# Sheet3.net
KiCad netlist of a schematic drawn in Altium Designer
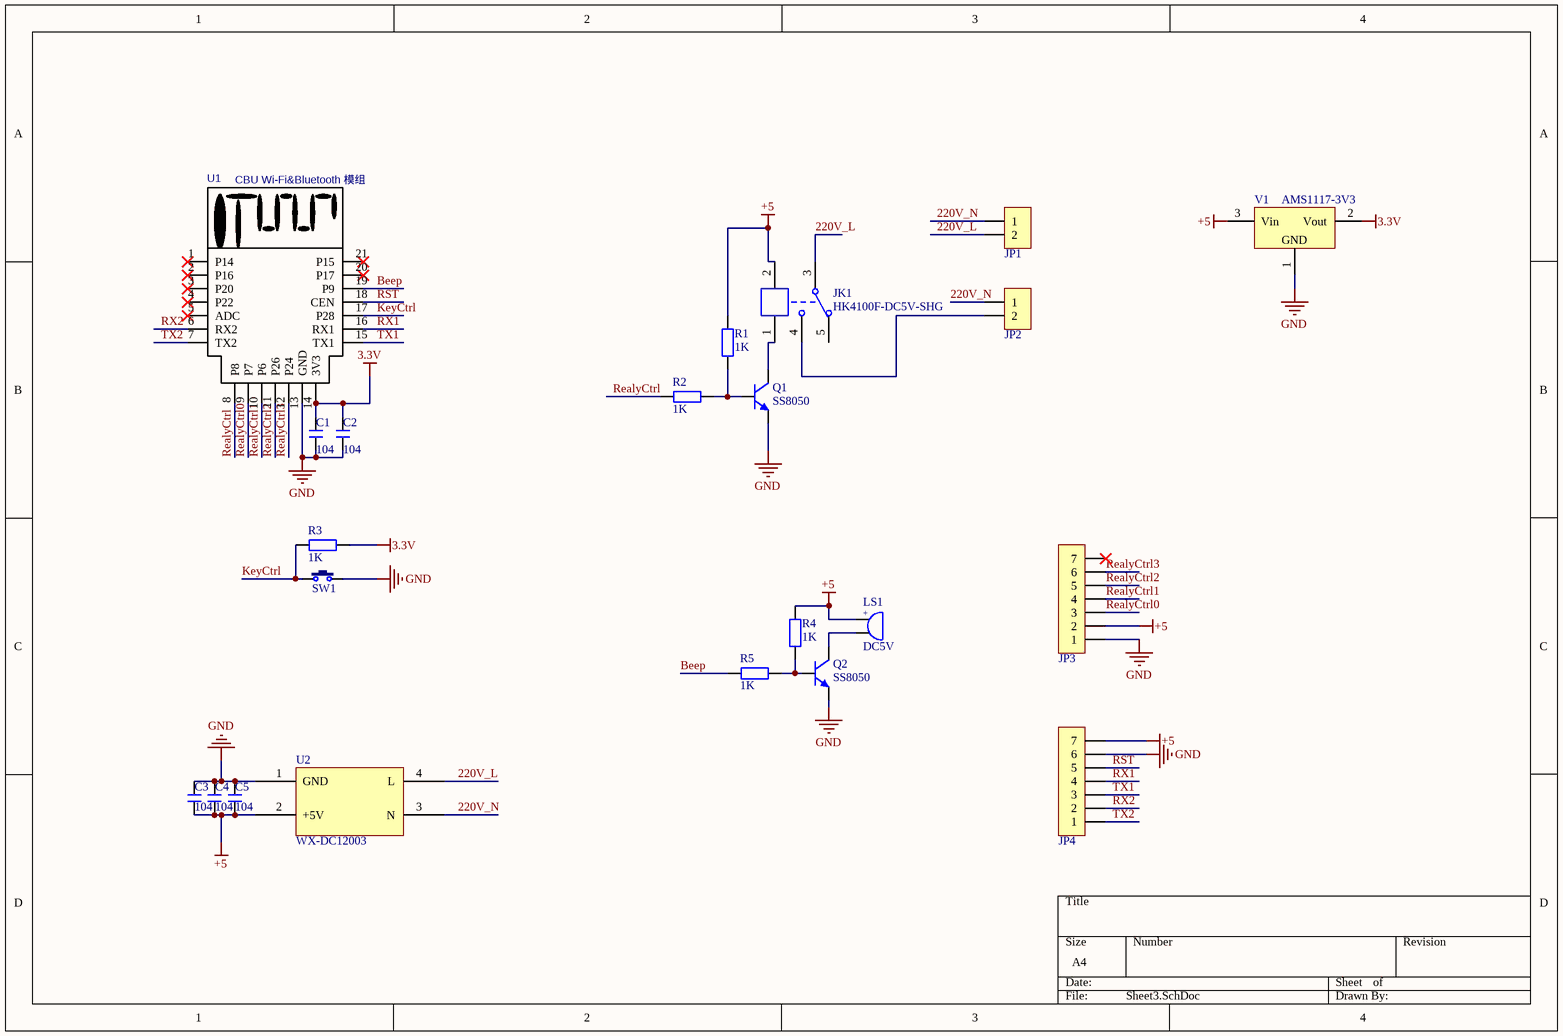
[diagram p0: Sheet3.SchDoc]

(export (version "E")
  (design (tool "Eeschema 10.0.6"))
  (components
    (comp (ref "C1")
      (value "104")
      (footprint "C 0805_M")
      (description "无极性贴片电容")
      (fields (field (name "版权归属") "源创客"))
      (libsource (lib "3.1   - 电阻-电容-电感") (part "C"))
    )
    (comp (ref "C2")
      (value "104")
      (footprint "C 0805_M")
      (description "无极性贴片电容")
      (fields (field (name "版权归属") "源创客"))
      (libsource (lib "3.1   - 电阻-电容-电感") (part "C"))
    )
    (comp (ref "C3")
      (value "104")
      (footprint "C 0805_M")
      (description "无极性贴片电容")
      (fields (field (name "版权归属") "源创客"))
      (libsource (lib "3.1   - 电阻-电容-电感") (part "C"))
    )
    (comp (ref "C4")
      (value "104")
      (footprint "C 0805_M")
      (description "无极性贴片电容")
      (fields (field (name "版权归属") "源创客"))
      (libsource (lib "3.1   - 电阻-电容-电感") (part "C"))
    )
    (comp (ref "C5")
      (value "104")
      (footprint "C 0805_M")
      (description "无极性贴片电容")
      (fields (field (name "版权归属") "源创客"))
      (libsource (lib "3.1   - 电阻-电容-电感") (part "C"))
    )
    (comp (ref "JK1")
      (value "HK4100F-DC5V-SHG")
      (footprint "HK4100F")
      (description "一组转换")
      (fields (field (name "版权归属") "源创客"))
      (libsource (lib "7.1   - 继电器") (part "HK4100F"))
    )
    (comp (ref "JP1")
      (value "HDR-1X2")
      (footprint "KF128-3.81-2P")
      (description "2P接插件")
      (fields (field (name "版权归属") "源创客"))
      (libsource (lib "4.7   - 接插件-脚距3.81") (part "Header 2"))
    )
    (comp (ref "JP2")
      (value "HDR-1X2")
      (footprint "KF128-3.81-2P")
      (description "2P接插件")
      (fields (field (name "版权归属") "源创客"))
      (libsource (lib "4.7   - 接插件-脚距3.81") (part "Header 2"))
    )
    (comp (ref "JP3")
      (value "HDR-1X7")
      (footprint "HDR2.54-M-LI-7P")
      (description "7P接插件")
      (fields (field (name "版权归属") "源创客"))
      (libsource (lib "4.5   - 接插件-脚距2.54") (part "Header 7"))
    )
    (comp (ref "JP4")
      (value "HDR-1X7")
      (footprint "HDR2.54-M-LI-7P")
      (description "7P接插件")
      (fields (field (name "版权归属") "源创客"))
      (libsource (lib "4.5   - 接插件-脚距2.54") (part "Header 7"))
    )
    (comp (ref "LS1")
      (value "DC5V")
      (footprint "BEEP 7.6X12X7.5")
      (description "蜂鸣器")
      (fields (field (name "版权归属") "源创客"))
      (libsource (lib "15.1 - 未分类器件") (part "BEEP"))
    )
    (comp (ref "Q1")
      (value "SS8050")
      (footprint "SOT23-3M")
      (description "高频放大-NPN型")
      (fields (field (name "版权归属") "源创客"))
      (libsource (lib "6.2   - 三极管") (part "8050-SMD"))
    )
    (comp (ref "Q2")
      (value "SS8050")
      (footprint "SOT23-3M")
      (description "高频放大-NPN型")
      (fields (field (name "版权归属") "源创客"))
      (libsource (lib "6.2   - 三极管") (part "8050-SMD"))
    )
    (comp (ref "R1")
      (value "1K")
      (footprint "R 0805_M")
      (description "贴片电阻")
      (fields (field (name "版权归属") "源创客"))
      (libsource (lib "3.1   - 电阻-电容-电感") (part "R"))
    )
    (comp (ref "R2")
      (value "1K")
      (footprint "R 0805_M")
      (description "贴片电阻")
      (fields (field (name "版权归属") "源创客"))
      (libsource (lib "3.1   - 电阻-电容-电感") (part "R"))
    )
    (comp (ref "R3")
      (value "1K")
      (footprint "R 0805_M")
      (description "贴片电阻")
      (fields (field (name "版权归属") "源创客"))
      (libsource (lib "3.1   - 电阻-电容-电感") (part "R"))
    )
    (comp (ref "R4")
      (value "1K")
      (footprint "R 0805_M")
      (description "贴片电阻")
      (fields (field (name "版权归属") "源创客"))
      (libsource (lib "3.1   - 电阻-电容-电感") (part "R"))
    )
    (comp (ref "R5")
      (value "1K")
      (footprint "R 0805_M")
      (description "贴片电阻")
      (fields (field (name "版权归属") "源创客"))
      (libsource (lib "3.1   - 电阻-电容-电感") (part "R"))
    )
    (comp (ref "SW1")
      (value "3x6x5")
      (footprint "TSW SMD-3*6*2.5")
      (description "3x6轻触开关")
      (fields (field (name "版权归属") "源创客"))
      (libsource (lib "5.1   - 按键-开关") (part "TSW 3x6"))
    )
    (comp (ref "U1")
      (value "CBU Wi-Fi&Bluetooth 模组")
      (footprint "CBU WIFI&BLUETOOTH")
      (fields (field (name "CONTRIBUTOR") "chenlf"))
      (libsource (lib "13.1 - 模块") (part "CBU"))
    )
    (comp (ref "U2")
      (value "WX-DC12003")
      (footprint "WX-DC12003")
      (description "wx-DC12003 220V转5V模块")
      (libsource (lib "封装") (part "WX-DC12003"))
    )
    (comp (ref "V1")
      (value "AMS1117-3V3")
      (footprint "SOT223_L")
      (description "三端稳压芯片")
      (fields (field (name "版权归属") "源创客"))
      (libsource (lib "1.3   - 电源类芯片") (part "AMS1117"))
    )
  )
  (nets
    (net (code "1") (name "+5") (class "Default")
      (node (ref "C3") (pin "1") (pinfunction "1_1") (pintype "passive"))
      (node (ref "C4") (pin "1") (pinfunction "1_1") (pintype "passive"))
      (node (ref "C5") (pin "1") (pinfunction "1_1") (pintype "passive"))
      (node (ref "JK1") (pin "2") (pinfunction "2_2") (pintype "passive"))
      (node (ref "JP3") (pin "2") (pinfunction "2_2") (pintype "passive"))
      (node (ref "JP4") (pin "7") (pinfunction "7_7") (pintype "passive"))
      (node (ref "LS1") (pin "1") (pinfunction "1_1") (pintype "passive"))
      (node (ref "R1") (pin "2") (pinfunction "2_2") (pintype "passive"))
      (node (ref "R4") (pin "2") (pinfunction "2_2") (pintype "passive"))
      (node (ref "U2") (pin "2") (pinfunction "+5V_2") (pintype "passive"))
      (node (ref "V1") (pin "3") (pinfunction "Vin_3") (pintype "passive"))
    )
    (net (code "2") (name "/220V_L") (class "Default")
      (node (ref "JK1") (pin "3") (pinfunction "3_3") (pintype "passive"))
      (node (ref "JP1") (pin "2") (pinfunction "2_2") (pintype "passive"))
      (node (ref "U2") (pin "4") (pinfunction "L_4") (pintype "passive"))
    )
    (net (code "3") (name "/220V_N") (class "Default")
      (node (ref "JP1") (pin "1") (pinfunction "1_1") (pintype "passive"))
      (node (ref "JP2") (pin "1") (pinfunction "1_1") (pintype "passive"))
      (node (ref "U2") (pin "3") (pinfunction "N_3") (pintype "passive"))
    )
    (net (code "4") (name "/Beep") (class "Default")
      (node (ref "R5") (pin "1") (pinfunction "1_1") (pintype "passive"))
      (node (ref "U1") (pin "19") (pinfunction "P9_19") (pintype "passive"))
    )
    (net (code "5") (name "/KeyCtrl") (class "Default")
      (node (ref "R3") (pin "2") (pinfunction "2_2") (pintype "passive"))
      (node (ref "SW1") (pin "1") (pinfunction "1_1") (pintype "passive"))
      (node (ref "U1") (pin "17") (pinfunction "P28_17") (pintype "passive"))
    )
    (net (code "6") (name "/RST") (class "Default")
      (node (ref "JP4") (pin "5") (pinfunction "5_5") (pintype "passive"))
      (node (ref "U1") (pin "18") (pinfunction "CEN_18") (pintype "passive"))
    )
    (net (code "7") (name "/RX1") (class "Default")
      (node (ref "JP4") (pin "4") (pinfunction "4_4") (pintype "passive"))
      (node (ref "U1") (pin "16") (pinfunction "RX1_16") (pintype "passive"))
    )
    (net (code "8") (name "/RX2") (class "Default")
      (node (ref "JP4") (pin "2") (pinfunction "2_2") (pintype "passive"))
      (node (ref "U1") (pin "6") (pinfunction "RX2_6") (pintype "passive"))
    )
    (net (code "9") (name "/RealyCtrl") (class "Default")
      (node (ref "R2") (pin "1") (pinfunction "1_1") (pintype "passive"))
      (node (ref "U1") (pin "8") (pinfunction "P8_8") (pintype "passive"))
    )
    (net (code "10") (name "/RealyCtrl0") (class "Default")
      (node (ref "JP3") (pin "3") (pinfunction "3_3") (pintype "passive"))
      (node (ref "U1") (pin "9") (pinfunction "P7_9") (pintype "passive"))
    )
    (net (code "11") (name "/RealyCtrl1") (class "Default")
      (node (ref "JP3") (pin "4") (pinfunction "4_4") (pintype "passive"))
      (node (ref "U1") (pin "10") (pinfunction "P6_10") (pintype "passive"))
    )
    (net (code "12") (name "/RealyCtrl2") (class "Default")
      (node (ref "JP3") (pin "5") (pinfunction "5_5") (pintype "passive"))
      (node (ref "U1") (pin "11") (pinfunction "P26_11") (pintype "passive"))
    )
    (net (code "13") (name "/RealyCtrl3") (class "Default")
      (node (ref "JP3") (pin "6") (pinfunction "6_6") (pintype "passive"))
      (node (ref "U1") (pin "12") (pinfunction "P24_12") (pintype "passive"))
    )
    (net (code "14") (name "/TX1") (class "Default")
      (node (ref "JP4") (pin "3") (pinfunction "3_3") (pintype "passive"))
      (node (ref "U1") (pin "15") (pinfunction "TX1_15") (pintype "passive"))
    )
    (net (code "15") (name "/TX2") (class "Default")
      (node (ref "JP4") (pin "1") (pinfunction "1_1") (pintype "passive"))
      (node (ref "U1") (pin "7") (pinfunction "TX2_7") (pintype "passive"))
    )
    (net (code "16") (name "3.3V") (class "Default")
      (node (ref "C1") (pin "2") (pinfunction "2_2") (pintype "passive"))
      (node (ref "C2") (pin "2") (pinfunction "2_2") (pintype "passive"))
      (node (ref "R3") (pin "1") (pinfunction "1_1") (pintype "passive"))
      (node (ref "U1") (pin "14") (pinfunction "3V3_14") (pintype "passive"))
      (node (ref "V1") (pin "2") (pinfunction "Vout_2") (pintype "passive"))
    )
    (net (code "17") (name "GND") (class "Default")
      (node (ref "C1") (pin "1") (pinfunction "1_1") (pintype "passive"))
      (node (ref "C2") (pin "1") (pinfunction "1_1") (pintype "passive"))
      (node (ref "C3") (pin "2") (pinfunction "2_2") (pintype "passive"))
      (node (ref "C4") (pin "2") (pinfunction "2_2") (pintype "passive"))
      (node (ref "C5") (pin "2") (pinfunction "2_2") (pintype "passive"))
      (node (ref "JP3") (pin "1") (pinfunction "1_1") (pintype "passive"))
      (node (ref "JP4") (pin "6") (pinfunction "6_6") (pintype "passive"))
      (node (ref "Q1") (pin "2") (pinfunction "E_2") (pintype "passive"))
      (node (ref "Q2") (pin "2") (pinfunction "E_2") (pintype "passive"))
      (node (ref "SW1") (pin "2") (pinfunction "2_2") (pintype "passive"))
      (node (ref "U1") (pin "13") (pinfunction "GND_13") (pintype "passive"))
      (node (ref "U2") (pin "1") (pinfunction "GND_1") (pintype "passive"))
      (node (ref "V1") (pin "1") (pinfunction "GND_1") (pintype "passive"))
    )
    (net (code "18") (name "Net-(JK1-Pad4)") (class "Default")
      (node (ref "JK1") (pin "4") (pinfunction "4_4") (pintype "passive"))
      (node (ref "JP2") (pin "2") (pinfunction "2_2") (pintype "passive"))
    )
    (net (code "19") (name "Net-(Q1-B)") (class "Default")
      (node (ref "Q1") (pin "1") (pinfunction "B_1") (pintype "passive"))
      (node (ref "R1") (pin "1") (pinfunction "1_1") (pintype "passive"))
      (node (ref "R2") (pin "2") (pinfunction "2_2") (pintype "passive"))
    )
    (net (code "20") (name "Net-(Q1-C)") (class "Default")
      (node (ref "JK1") (pin "1") (pinfunction "1_1") (pintype "passive"))
      (node (ref "Q1") (pin "3") (pinfunction "C_3") (pintype "passive"))
    )
    (net (code "21") (name "Net-(Q2-B)") (class "Default")
      (node (ref "Q2") (pin "1") (pinfunction "B_1") (pintype "passive"))
      (node (ref "R4") (pin "1") (pinfunction "1_1") (pintype "passive"))
      (node (ref "R5") (pin "2") (pinfunction "2_2") (pintype "passive"))
    )
    (net (code "22") (name "Net-(Q2-C)") (class "Default")
      (node (ref "LS1") (pin "2") (pinfunction "2_2") (pintype "passive"))
      (node (ref "Q2") (pin "3") (pinfunction "C_3") (pintype "passive"))
    )
    (net (code "23") (name "unconnected-(JK1-Pad5)") (class "Default")
      (node (ref "JK1") (pin "5") (pinfunction "5_5") (pintype "passive"))
    )
    (net (code "24") (name "unconnected-(JP3-Pad7)") (class "Default")
      (node (ref "JP3") (pin "7") (pinfunction "7_7") (pintype "passive+no_connect"))
    )
    (net (code "25") (name "unconnected-(U1-ADC-Pad5)") (class "Default")
      (node (ref "U1") (pin "5") (pinfunction "ADC_5") (pintype "passive+no_connect"))
    )
    (net (code "26") (name "unconnected-(U1-P14-Pad1)") (class "Default")
      (node (ref "U1") (pin "1") (pinfunction "P14_1") (pintype "passive+no_connect"))
    )
    (net (code "27") (name "unconnected-(U1-P15-Pad21)") (class "Default")
      (node (ref "U1") (pin "21") (pinfunction "P15_21") (pintype "passive+no_connect"))
    )
    (net (code "28") (name "unconnected-(U1-P16-Pad2)") (class "Default")
      (node (ref "U1") (pin "2") (pinfunction "P16_2") (pintype "passive+no_connect"))
    )
    (net (code "29") (name "unconnected-(U1-P17-Pad20)") (class "Default")
      (node (ref "U1") (pin "20") (pinfunction "P17_20") (pintype "passive+no_connect"))
    )
    (net (code "30") (name "unconnected-(U1-P20-Pad3)") (class "Default")
      (node (ref "U1") (pin "3") (pinfunction "P20_3") (pintype "passive+no_connect"))
    )
    (net (code "31") (name "unconnected-(U1-P22-Pad4)") (class "Default")
      (node (ref "U1") (pin "4") (pinfunction "P22_4") (pintype "passive+no_connect"))
    )
  )
)
